# Main.net
KiCad netlist of a schematic drawn in Altium Designer
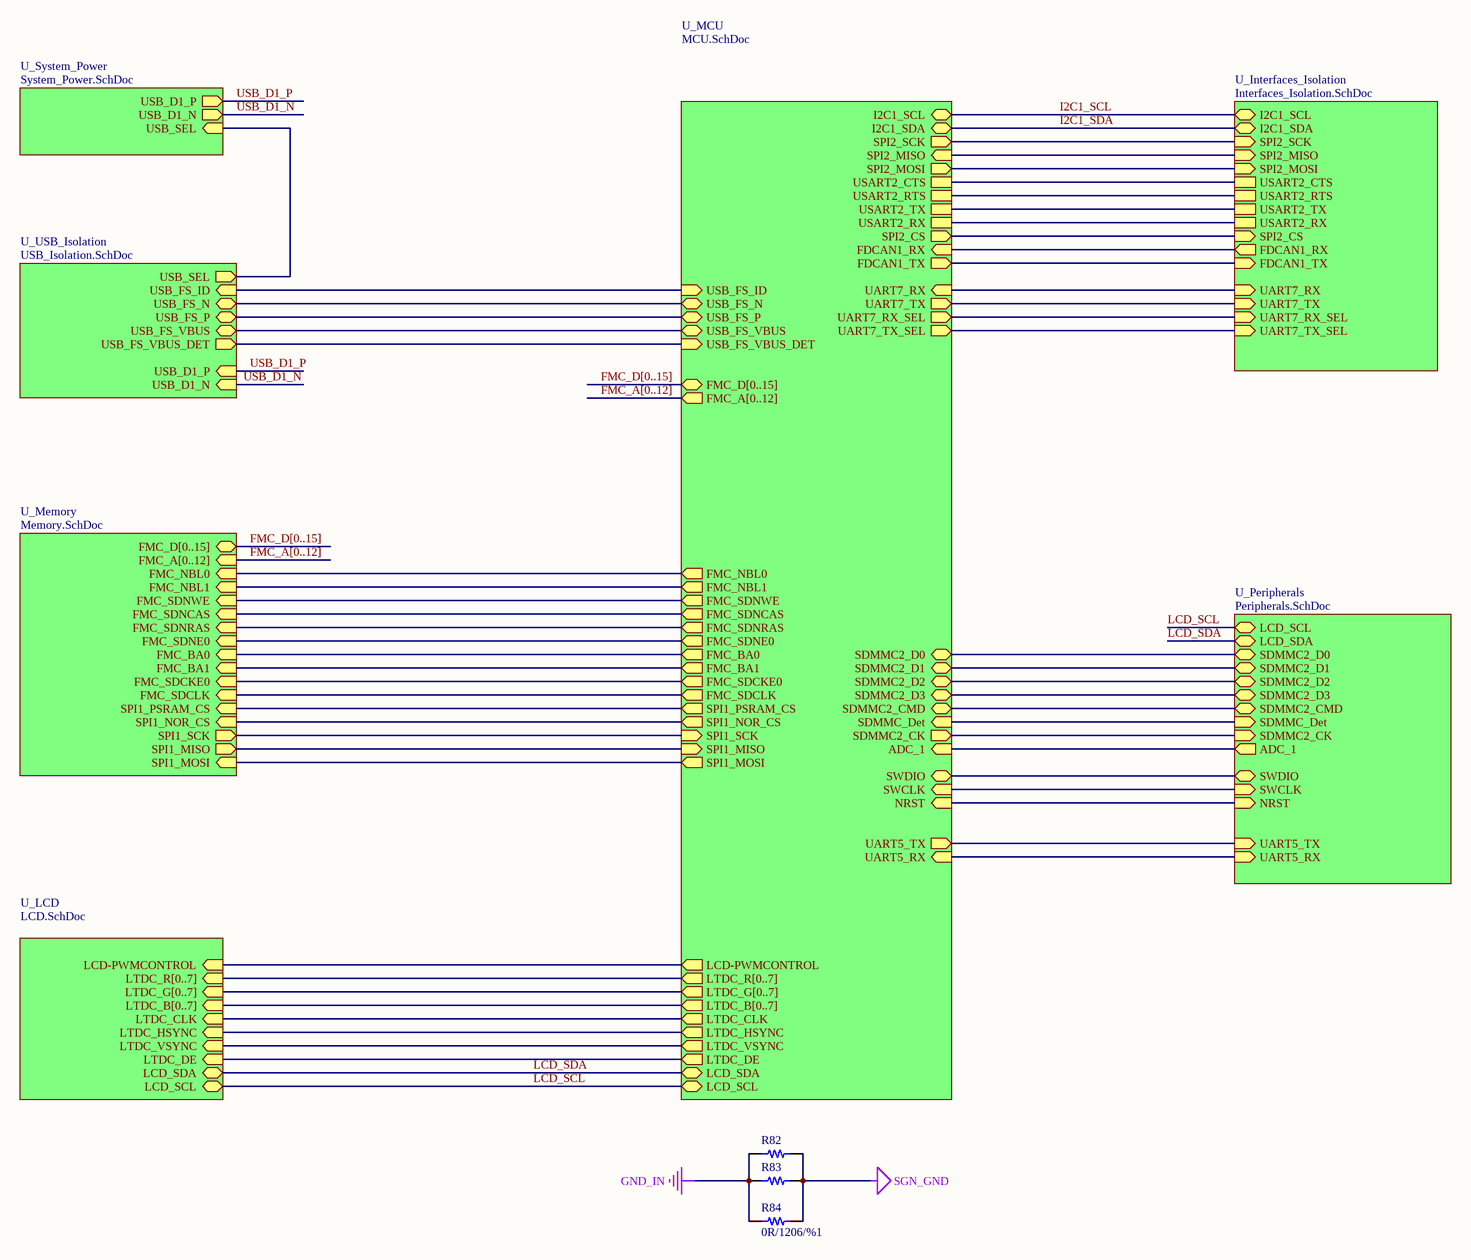
[diagram p0: Main.SchDoc]

(export (version "E")
  (design (tool "Eeschema 10.0.6"))
  (components
    (comp (ref "R82") (value "0R/1206/%1") (footprint "1206_res") (libsource (lib "IM_v1.0") (part "RES")))
    (comp (ref "R83") (value "0R/1206/%1") (footprint "1206_res") (libsource (lib "IM_v1.0") (part "RES")))
    (comp (ref "R84") (value "0R/1206/%1") (footprint "1206_res") (libsource (lib "IM_v1.0") (part "RES")))
  )
  (nets
    (net (code "94") (name "GND_IN") (class "Default")
      (node (ref "R82") (pin "2") (pinfunction "2_2") (pintype "passive"))
      (node (ref "R83") (pin "2") (pinfunction "2_2") (pintype "passive"))
      (node (ref "R84") (pin "2") (pinfunction "2_2") (pintype "passive"))
    )
    (net (code "95") (name "SGN_GND") (class "Default")
      (node (ref "R82") (pin "1") (pinfunction "1_1") (pintype "passive"))
      (node (ref "R83") (pin "1") (pinfunction "1_1") (pintype "passive"))
      (node (ref "R84") (pin "1") (pinfunction "1_1") (pintype "passive"))
    )
  )
)
